# main.net
KiCad netlist of a schematic drawn in Altium Designer
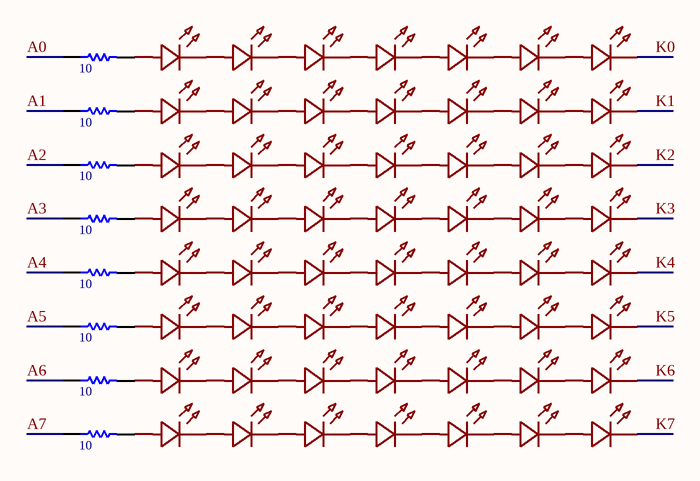
[diagram p0: main.SchDoc]

(export (version "E")
  (design (tool "Eeschema 10.0.6"))
  (components
    (comp (ref "R1")
      (value "10")
      (footprint "R2512")
      (description "10R 2512")
      (fields (field (name "LCSC PART NUMBER") "C173291"))
      (libsource (lib "Miscellaneous Devices") (part "RES"))
    )
    (comp (ref "R2")
      (value "10")
      (footprint "R2512")
      (description "10R 2512")
      (fields (field (name "LCSC PART NUMBER") "C173291"))
      (libsource (lib "Miscellaneous Devices") (part "RES"))
    )
    (comp (ref "R3")
      (value "10")
      (footprint "R2512")
      (description "10R 2512")
      (fields (field (name "LCSC PART NUMBER") "C173291"))
      (libsource (lib "Miscellaneous Devices") (part "RES"))
    )
    (comp (ref "R4")
      (value "10")
      (footprint "R2512")
      (description "10R 2512")
      (fields (field (name "LCSC PART NUMBER") "C173291"))
      (libsource (lib "Miscellaneous Devices") (part "RES"))
    )
    (comp (ref "R5")
      (value "10")
      (footprint "R2512")
      (description "10R 2512")
      (fields (field (name "LCSC PART NUMBER") "C173291"))
      (libsource (lib "Miscellaneous Devices") (part "RES"))
    )
    (comp (ref "R6")
      (value "10")
      (footprint "R2512")
      (description "10R 2512")
      (fields (field (name "LCSC PART NUMBER") "C173291"))
      (libsource (lib "Miscellaneous Devices") (part "RES"))
    )
    (comp (ref "R7")
      (value "10")
      (footprint "R2512")
      (description "10R 2512")
      (fields (field (name "LCSC PART NUMBER") "C173291"))
      (libsource (lib "Miscellaneous Devices") (part "RES"))
    )
    (comp (ref "R8")
      (value "10")
      (footprint "R2512")
      (description "10R 2512")
      (fields (field (name "LCSC PART NUMBER") "C173291"))
      (libsource (lib "Miscellaneous Devices") (part "RES"))
    )
    (comp (ref "U1")
      (value "~")
      (footprint "LED-SMD_7030")
      (libsource (lib "Schlib1") (part "XL-C3570P8S11-62C3C2"))
    )
    (comp (ref "U2")
      (value "~")
      (footprint "LED-SMD_7030")
      (libsource (lib "Schlib1") (part "XL-C3570P8S11-62C3C2"))
    )
    (comp (ref "U3")
      (value "~")
      (footprint "LED-SMD_7030")
      (libsource (lib "Schlib1") (part "XL-C3570P8S11-62C3C2"))
    )
    (comp (ref "U4")
      (value "~")
      (footprint "LED-SMD_7030")
      (libsource (lib "Schlib1") (part "XL-C3570P8S11-62C3C2"))
    )
    (comp (ref "U5")
      (value "~")
      (footprint "LED-SMD_7030")
      (libsource (lib "Schlib1") (part "XL-C3570P8S11-62C3C2"))
    )
    (comp (ref "U6")
      (value "~")
      (footprint "LED-SMD_7030")
      (libsource (lib "Schlib1") (part "XL-C3570P8S11-62C3C2"))
    )
    (comp (ref "U7")
      (value "~")
      (footprint "LED-SMD_7030")
      (libsource (lib "Schlib1") (part "XL-C3570P8S11-62C3C2"))
    )
    (comp (ref "U8")
      (value "~")
      (footprint "LED-SMD_7030")
      (libsource (lib "Schlib1") (part "XL-C3570P8S11-62C3C2"))
    )
    (comp (ref "U9")
      (value "~")
      (footprint "LED-SMD_7030")
      (libsource (lib "Schlib1") (part "XL-C3570P8S11-62C3C2"))
    )
    (comp (ref "U10")
      (value "~")
      (footprint "LED-SMD_7030")
      (libsource (lib "Schlib1") (part "XL-C3570P8S11-62C3C2"))
    )
    (comp (ref "U11")
      (value "~")
      (footprint "LED-SMD_7030")
      (libsource (lib "Schlib1") (part "XL-C3570P8S11-62C3C2"))
    )
    (comp (ref "U12")
      (value "~")
      (footprint "LED-SMD_7030")
      (libsource (lib "Schlib1") (part "XL-C3570P8S11-62C3C2"))
    )
    (comp (ref "U13")
      (value "~")
      (footprint "LED-SMD_7030")
      (libsource (lib "Schlib1") (part "XL-C3570P8S11-62C3C2"))
    )
    (comp (ref "U14")
      (value "~")
      (footprint "LED-SMD_7030")
      (libsource (lib "Schlib1") (part "XL-C3570P8S11-62C3C2"))
    )
    (comp (ref "U15")
      (value "~")
      (footprint "LED-SMD_7030")
      (libsource (lib "Schlib1") (part "XL-C3570P8S11-62C3C2"))
    )
    (comp (ref "U16")
      (value "~")
      (footprint "LED-SMD_7030")
      (libsource (lib "Schlib1") (part "XL-C3570P8S11-62C3C2"))
    )
    (comp (ref "U17")
      (value "~")
      (footprint "LED-SMD_7030")
      (libsource (lib "Schlib1") (part "XL-C3570P8S11-62C3C2"))
    )
    (comp (ref "U18")
      (value "~")
      (footprint "LED-SMD_7030")
      (libsource (lib "Schlib1") (part "XL-C3570P8S11-62C3C2"))
    )
    (comp (ref "U19")
      (value "~")
      (footprint "LED-SMD_7030")
      (libsource (lib "Schlib1") (part "XL-C3570P8S11-62C3C2"))
    )
    (comp (ref "U20")
      (value "~")
      (footprint "LED-SMD_7030")
      (libsource (lib "Schlib1") (part "XL-C3570P8S11-62C3C2"))
    )
    (comp (ref "U21")
      (value "~")
      (footprint "LED-SMD_7030")
      (libsource (lib "Schlib1") (part "XL-C3570P8S11-62C3C2"))
    )
    (comp (ref "U22")
      (value "~")
      (footprint "LED-SMD_7030")
      (libsource (lib "Schlib1") (part "XL-C3570P8S11-62C3C2"))
    )
    (comp (ref "U23")
      (value "~")
      (footprint "LED-SMD_7030")
      (libsource (lib "Schlib1") (part "XL-C3570P8S11-62C3C2"))
    )
    (comp (ref "U24")
      (value "~")
      (footprint "LED-SMD_7030")
      (libsource (lib "Schlib1") (part "XL-C3570P8S11-62C3C2"))
    )
    (comp (ref "U25")
      (value "~")
      (footprint "LED-SMD_7030")
      (libsource (lib "Schlib1") (part "XL-C3570P8S11-62C3C2"))
    )
    (comp (ref "U26")
      (value "~")
      (footprint "LED-SMD_7030")
      (libsource (lib "Schlib1") (part "XL-C3570P8S11-62C3C2"))
    )
    (comp (ref "U27")
      (value "~")
      (footprint "LED-SMD_7030")
      (libsource (lib "Schlib1") (part "XL-C3570P8S11-62C3C2"))
    )
    (comp (ref "U28")
      (value "~")
      (footprint "LED-SMD_7030")
      (libsource (lib "Schlib1") (part "XL-C3570P8S11-62C3C2"))
    )
    (comp (ref "U29")
      (value "~")
      (footprint "LED-SMD_7030")
      (libsource (lib "Schlib1") (part "XL-C3570P8S11-62C3C2"))
    )
    (comp (ref "U30")
      (value "~")
      (footprint "LED-SMD_7030")
      (libsource (lib "Schlib1") (part "XL-C3570P8S11-62C3C2"))
    )
    (comp (ref "U31")
      (value "~")
      (footprint "LED-SMD_7030")
      (libsource (lib "Schlib1") (part "XL-C3570P8S11-62C3C2"))
    )
    (comp (ref "U32")
      (value "~")
      (footprint "LED-SMD_7030")
      (libsource (lib "Schlib1") (part "XL-C3570P8S11-62C3C2"))
    )
    (comp (ref "U33")
      (value "~")
      (footprint "LED-SMD_7030")
      (libsource (lib "Schlib1") (part "XL-C3570P8S11-62C3C2"))
    )
    (comp (ref "U34")
      (value "~")
      (footprint "LED-SMD_7030")
      (libsource (lib "Schlib1") (part "XL-C3570P8S11-62C3C2"))
    )
    (comp (ref "U35")
      (value "~")
      (footprint "LED-SMD_7030")
      (libsource (lib "Schlib1") (part "XL-C3570P8S11-62C3C2"))
    )
    (comp (ref "U36")
      (value "~")
      (footprint "LED-SMD_7030")
      (libsource (lib "Schlib1") (part "XL-C3570P8S11-62C3C2"))
    )
    (comp (ref "U37")
      (value "~")
      (footprint "LED-SMD_7030")
      (libsource (lib "Schlib1") (part "XL-C3570P8S11-62C3C2"))
    )
    (comp (ref "U38")
      (value "~")
      (footprint "LED-SMD_7030")
      (libsource (lib "Schlib1") (part "XL-C3570P8S11-62C3C2"))
    )
    (comp (ref "U39")
      (value "~")
      (footprint "LED-SMD_7030")
      (libsource (lib "Schlib1") (part "XL-C3570P8S11-62C3C2"))
    )
    (comp (ref "U40")
      (value "~")
      (footprint "LED-SMD_7030")
      (libsource (lib "Schlib1") (part "XL-C3570P8S11-62C3C2"))
    )
    (comp (ref "U41")
      (value "~")
      (footprint "LED-SMD_7030")
      (libsource (lib "Schlib1") (part "XL-C3570P8S11-62C3C2"))
    )
    (comp (ref "U42")
      (value "~")
      (footprint "LED-SMD_7030")
      (libsource (lib "Schlib1") (part "XL-C3570P8S11-62C3C2"))
    )
    (comp (ref "U43")
      (value "~")
      (footprint "LED-SMD_7030")
      (libsource (lib "Schlib1") (part "XL-C3570P8S11-62C3C2"))
    )
    (comp (ref "U44")
      (value "~")
      (footprint "LED-SMD_7030")
      (libsource (lib "Schlib1") (part "XL-C3570P8S11-62C3C2"))
    )
    (comp (ref "U45")
      (value "~")
      (footprint "LED-SMD_7030")
      (libsource (lib "Schlib1") (part "XL-C3570P8S11-62C3C2"))
    )
    (comp (ref "U46")
      (value "~")
      (footprint "LED-SMD_7030")
      (libsource (lib "Schlib1") (part "XL-C3570P8S11-62C3C2"))
    )
    (comp (ref "U47")
      (value "~")
      (footprint "LED-SMD_7030")
      (libsource (lib "Schlib1") (part "XL-C3570P8S11-62C3C2"))
    )
    (comp (ref "U48")
      (value "~")
      (footprint "LED-SMD_7030")
      (libsource (lib "Schlib1") (part "XL-C3570P8S11-62C3C2"))
    )
    (comp (ref "U49")
      (value "~")
      (footprint "LED-SMD_7030")
      (libsource (lib "Schlib1") (part "XL-C3570P8S11-62C3C2"))
    )
    (comp (ref "U50")
      (value "~")
      (footprint "LED-SMD_7030")
      (libsource (lib "Schlib1") (part "XL-C3570P8S11-62C3C2"))
    )
    (comp (ref "U51")
      (value "~")
      (footprint "LED-SMD_7030")
      (libsource (lib "Schlib1") (part "XL-C3570P8S11-62C3C2"))
    )
    (comp (ref "U52")
      (value "~")
      (footprint "LED-SMD_7030")
      (libsource (lib "Schlib1") (part "XL-C3570P8S11-62C3C2"))
    )
    (comp (ref "U53")
      (value "~")
      (footprint "LED-SMD_7030")
      (libsource (lib "Schlib1") (part "XL-C3570P8S11-62C3C2"))
    )
    (comp (ref "U54")
      (value "~")
      (footprint "LED-SMD_7030")
      (libsource (lib "Schlib1") (part "XL-C3570P8S11-62C3C2"))
    )
    (comp (ref "U55")
      (value "~")
      (footprint "LED-SMD_7030")
      (libsource (lib "Schlib1") (part "XL-C3570P8S11-62C3C2"))
    )
    (comp (ref "U56")
      (value "~")
      (footprint "LED-SMD_7030")
      (libsource (lib "Schlib1") (part "XL-C3570P8S11-62C3C2"))
    )
  )
  (nets
    (net (code "1") (name "/A0") (class "Default")
      (node (ref "R1") (pin "1") (pinfunction "1_1") (pintype "passive"))
    )
    (net (code "2") (name "/A1") (class "Default")
      (node (ref "R2") (pin "1") (pinfunction "1_1") (pintype "passive"))
    )
    (net (code "3") (name "/A2") (class "Default")
      (node (ref "R3") (pin "1") (pinfunction "1_1") (pintype "passive"))
    )
    (net (code "4") (name "/A3") (class "Default")
      (node (ref "R4") (pin "1") (pinfunction "1_1") (pintype "passive"))
    )
    (net (code "5") (name "/A4") (class "Default")
      (node (ref "R5") (pin "1") (pinfunction "1_1") (pintype "passive"))
    )
    (net (code "6") (name "/A5") (class "Default")
      (node (ref "R6") (pin "1") (pinfunction "1_1") (pintype "passive"))
    )
    (net (code "7") (name "/A6") (class "Default")
      (node (ref "R7") (pin "1") (pinfunction "1_1") (pintype "passive"))
    )
    (net (code "8") (name "/A7") (class "Default")
      (node (ref "R8") (pin "1") (pinfunction "1_1") (pintype "passive"))
    )
    (net (code "9") (name "/K0") (class "Default")
      (node (ref "U7") (pin "2") (pinfunction "K_2") (pintype "passive"))
    )
    (net (code "10") (name "/K1") (class "Default")
      (node (ref "U14") (pin "2") (pinfunction "K_2") (pintype "passive"))
    )
    (net (code "11") (name "/K2") (class "Default")
      (node (ref "U21") (pin "2") (pinfunction "K_2") (pintype "passive"))
    )
    (net (code "12") (name "/K3") (class "Default")
      (node (ref "U28") (pin "2") (pinfunction "K_2") (pintype "passive"))
    )
    (net (code "13") (name "/K4") (class "Default")
      (node (ref "U35") (pin "2") (pinfunction "K_2") (pintype "passive"))
    )
    (net (code "14") (name "/K5") (class "Default")
      (node (ref "U42") (pin "2") (pinfunction "K_2") (pintype "passive"))
    )
    (net (code "15") (name "/K6") (class "Default")
      (node (ref "U49") (pin "2") (pinfunction "K_2") (pintype "passive"))
    )
    (net (code "16") (name "/K7") (class "Default")
      (node (ref "U56") (pin "2") (pinfunction "K_2") (pintype "passive"))
    )
    (net (code "17") (name "Net-(U1-A)") (class "Default")
      (node (ref "R1") (pin "2") (pinfunction "2_2") (pintype "passive"))
      (node (ref "U1") (pin "1") (pinfunction "A_1") (pintype "passive"))
    )
    (net (code "18") (name "Net-(U1-K)") (class "Default")
      (node (ref "U1") (pin "2") (pinfunction "K_2") (pintype "passive"))
      (node (ref "U2") (pin "1") (pinfunction "A_1") (pintype "passive"))
    )
    (net (code "19") (name "Net-(U2-K)") (class "Default")
      (node (ref "U2") (pin "2") (pinfunction "K_2") (pintype "passive"))
      (node (ref "U3") (pin "1") (pinfunction "A_1") (pintype "passive"))
    )
    (net (code "20") (name "Net-(U3-K)") (class "Default")
      (node (ref "U3") (pin "2") (pinfunction "K_2") (pintype "passive"))
      (node (ref "U4") (pin "1") (pinfunction "A_1") (pintype "passive"))
    )
    (net (code "21") (name "Net-(U4-K)") (class "Default")
      (node (ref "U4") (pin "2") (pinfunction "K_2") (pintype "passive"))
      (node (ref "U5") (pin "1") (pinfunction "A_1") (pintype "passive"))
    )
    (net (code "22") (name "Net-(U5-K)") (class "Default")
      (node (ref "U5") (pin "2") (pinfunction "K_2") (pintype "passive"))
      (node (ref "U6") (pin "1") (pinfunction "A_1") (pintype "passive"))
    )
    (net (code "23") (name "Net-(U6-K)") (class "Default")
      (node (ref "U6") (pin "2") (pinfunction "K_2") (pintype "passive"))
      (node (ref "U7") (pin "1") (pinfunction "A_1") (pintype "passive"))
    )
    (net (code "24") (name "Net-(U8-A)") (class "Default")
      (node (ref "R2") (pin "2") (pinfunction "2_2") (pintype "passive"))
      (node (ref "U8") (pin "1") (pinfunction "A_1") (pintype "passive"))
    )
    (net (code "25") (name "Net-(U8-K)") (class "Default")
      (node (ref "U8") (pin "2") (pinfunction "K_2") (pintype "passive"))
      (node (ref "U9") (pin "1") (pinfunction "A_1") (pintype "passive"))
    )
    (net (code "26") (name "Net-(U10-A)") (class "Default")
      (node (ref "U10") (pin "1") (pinfunction "A_1") (pintype "passive"))
      (node (ref "U9") (pin "2") (pinfunction "K_2") (pintype "passive"))
    )
    (net (code "27") (name "Net-(U10-K)") (class "Default")
      (node (ref "U10") (pin "2") (pinfunction "K_2") (pintype "passive"))
      (node (ref "U11") (pin "1") (pinfunction "A_1") (pintype "passive"))
    )
    (net (code "28") (name "Net-(U11-K)") (class "Default")
      (node (ref "U11") (pin "2") (pinfunction "K_2") (pintype "passive"))
      (node (ref "U12") (pin "1") (pinfunction "A_1") (pintype "passive"))
    )
    (net (code "29") (name "Net-(U12-K)") (class "Default")
      (node (ref "U12") (pin "2") (pinfunction "K_2") (pintype "passive"))
      (node (ref "U13") (pin "1") (pinfunction "A_1") (pintype "passive"))
    )
    (net (code "30") (name "Net-(U13-K)") (class "Default")
      (node (ref "U13") (pin "2") (pinfunction "K_2") (pintype "passive"))
      (node (ref "U14") (pin "1") (pinfunction "A_1") (pintype "passive"))
    )
    (net (code "31") (name "Net-(U15-A)") (class "Default")
      (node (ref "R3") (pin "2") (pinfunction "2_2") (pintype "passive"))
      (node (ref "U15") (pin "1") (pinfunction "A_1") (pintype "passive"))
    )
    (net (code "32") (name "Net-(U15-K)") (class "Default")
      (node (ref "U15") (pin "2") (pinfunction "K_2") (pintype "passive"))
      (node (ref "U16") (pin "1") (pinfunction "A_1") (pintype "passive"))
    )
    (net (code "33") (name "Net-(U16-K)") (class "Default")
      (node (ref "U16") (pin "2") (pinfunction "K_2") (pintype "passive"))
      (node (ref "U17") (pin "1") (pinfunction "A_1") (pintype "passive"))
    )
    (net (code "34") (name "Net-(U17-K)") (class "Default")
      (node (ref "U17") (pin "2") (pinfunction "K_2") (pintype "passive"))
      (node (ref "U18") (pin "1") (pinfunction "A_1") (pintype "passive"))
    )
    (net (code "35") (name "Net-(U18-K)") (class "Default")
      (node (ref "U18") (pin "2") (pinfunction "K_2") (pintype "passive"))
      (node (ref "U19") (pin "1") (pinfunction "A_1") (pintype "passive"))
    )
    (net (code "36") (name "Net-(U19-K)") (class "Default")
      (node (ref "U19") (pin "2") (pinfunction "K_2") (pintype "passive"))
      (node (ref "U20") (pin "1") (pinfunction "A_1") (pintype "passive"))
    )
    (net (code "37") (name "Net-(U20-K)") (class "Default")
      (node (ref "U20") (pin "2") (pinfunction "K_2") (pintype "passive"))
      (node (ref "U21") (pin "1") (pinfunction "A_1") (pintype "passive"))
    )
    (net (code "38") (name "Net-(U22-A)") (class "Default")
      (node (ref "R4") (pin "2") (pinfunction "2_2") (pintype "passive"))
      (node (ref "U22") (pin "1") (pinfunction "A_1") (pintype "passive"))
    )
    (net (code "39") (name "Net-(U22-K)") (class "Default")
      (node (ref "U22") (pin "2") (pinfunction "K_2") (pintype "passive"))
      (node (ref "U23") (pin "1") (pinfunction "A_1") (pintype "passive"))
    )
    (net (code "40") (name "Net-(U23-K)") (class "Default")
      (node (ref "U23") (pin "2") (pinfunction "K_2") (pintype "passive"))
      (node (ref "U24") (pin "1") (pinfunction "A_1") (pintype "passive"))
    )
    (net (code "41") (name "Net-(U24-K)") (class "Default")
      (node (ref "U24") (pin "2") (pinfunction "K_2") (pintype "passive"))
      (node (ref "U25") (pin "1") (pinfunction "A_1") (pintype "passive"))
    )
    (net (code "42") (name "Net-(U25-K)") (class "Default")
      (node (ref "U25") (pin "2") (pinfunction "K_2") (pintype "passive"))
      (node (ref "U26") (pin "1") (pinfunction "A_1") (pintype "passive"))
    )
    (net (code "43") (name "Net-(U26-K)") (class "Default")
      (node (ref "U26") (pin "2") (pinfunction "K_2") (pintype "passive"))
      (node (ref "U27") (pin "1") (pinfunction "A_1") (pintype "passive"))
    )
    (net (code "44") (name "Net-(U27-K)") (class "Default")
      (node (ref "U27") (pin "2") (pinfunction "K_2") (pintype "passive"))
      (node (ref "U28") (pin "1") (pinfunction "A_1") (pintype "passive"))
    )
    (net (code "45") (name "Net-(U29-A)") (class "Default")
      (node (ref "R5") (pin "2") (pinfunction "2_2") (pintype "passive"))
      (node (ref "U29") (pin "1") (pinfunction "A_1") (pintype "passive"))
    )
    (net (code "46") (name "Net-(U29-K)") (class "Default")
      (node (ref "U29") (pin "2") (pinfunction "K_2") (pintype "passive"))
      (node (ref "U30") (pin "1") (pinfunction "A_1") (pintype "passive"))
    )
    (net (code "47") (name "Net-(U30-K)") (class "Default")
      (node (ref "U30") (pin "2") (pinfunction "K_2") (pintype "passive"))
      (node (ref "U31") (pin "1") (pinfunction "A_1") (pintype "passive"))
    )
    (net (code "48") (name "Net-(U31-K)") (class "Default")
      (node (ref "U31") (pin "2") (pinfunction "K_2") (pintype "passive"))
      (node (ref "U32") (pin "1") (pinfunction "A_1") (pintype "passive"))
    )
    (net (code "49") (name "Net-(U32-K)") (class "Default")
      (node (ref "U32") (pin "2") (pinfunction "K_2") (pintype "passive"))
      (node (ref "U33") (pin "1") (pinfunction "A_1") (pintype "passive"))
    )
    (net (code "50") (name "Net-(U33-K)") (class "Default")
      (node (ref "U33") (pin "2") (pinfunction "K_2") (pintype "passive"))
      (node (ref "U34") (pin "1") (pinfunction "A_1") (pintype "passive"))
    )
    (net (code "51") (name "Net-(U34-K)") (class "Default")
      (node (ref "U34") (pin "2") (pinfunction "K_2") (pintype "passive"))
      (node (ref "U35") (pin "1") (pinfunction "A_1") (pintype "passive"))
    )
    (net (code "52") (name "Net-(U36-A)") (class "Default")
      (node (ref "R6") (pin "2") (pinfunction "2_2") (pintype "passive"))
      (node (ref "U36") (pin "1") (pinfunction "A_1") (pintype "passive"))
    )
    (net (code "53") (name "Net-(U36-K)") (class "Default")
      (node (ref "U36") (pin "2") (pinfunction "K_2") (pintype "passive"))
      (node (ref "U37") (pin "1") (pinfunction "A_1") (pintype "passive"))
    )
    (net (code "54") (name "Net-(U37-K)") (class "Default")
      (node (ref "U37") (pin "2") (pinfunction "K_2") (pintype "passive"))
      (node (ref "U38") (pin "1") (pinfunction "A_1") (pintype "passive"))
    )
    (net (code "55") (name "Net-(U38-K)") (class "Default")
      (node (ref "U38") (pin "2") (pinfunction "K_2") (pintype "passive"))
      (node (ref "U39") (pin "1") (pinfunction "A_1") (pintype "passive"))
    )
    (net (code "56") (name "Net-(U39-K)") (class "Default")
      (node (ref "U39") (pin "2") (pinfunction "K_2") (pintype "passive"))
      (node (ref "U40") (pin "1") (pinfunction "A_1") (pintype "passive"))
    )
    (net (code "57") (name "Net-(U40-K)") (class "Default")
      (node (ref "U40") (pin "2") (pinfunction "K_2") (pintype "passive"))
      (node (ref "U41") (pin "1") (pinfunction "A_1") (pintype "passive"))
    )
    (net (code "58") (name "Net-(U41-K)") (class "Default")
      (node (ref "U41") (pin "2") (pinfunction "K_2") (pintype "passive"))
      (node (ref "U42") (pin "1") (pinfunction "A_1") (pintype "passive"))
    )
    (net (code "59") (name "Net-(U43-A)") (class "Default")
      (node (ref "R7") (pin "2") (pinfunction "2_2") (pintype "passive"))
      (node (ref "U43") (pin "1") (pinfunction "A_1") (pintype "passive"))
    )
    (net (code "60") (name "Net-(U43-K)") (class "Default")
      (node (ref "U43") (pin "2") (pinfunction "K_2") (pintype "passive"))
      (node (ref "U44") (pin "1") (pinfunction "A_1") (pintype "passive"))
    )
    (net (code "61") (name "Net-(U44-K)") (class "Default")
      (node (ref "U44") (pin "2") (pinfunction "K_2") (pintype "passive"))
      (node (ref "U45") (pin "1") (pinfunction "A_1") (pintype "passive"))
    )
    (net (code "62") (name "Net-(U45-K)") (class "Default")
      (node (ref "U45") (pin "2") (pinfunction "K_2") (pintype "passive"))
      (node (ref "U46") (pin "1") (pinfunction "A_1") (pintype "passive"))
    )
    (net (code "63") (name "Net-(U46-K)") (class "Default")
      (node (ref "U46") (pin "2") (pinfunction "K_2") (pintype "passive"))
      (node (ref "U47") (pin "1") (pinfunction "A_1") (pintype "passive"))
    )
    (net (code "64") (name "Net-(U47-K)") (class "Default")
      (node (ref "U47") (pin "2") (pinfunction "K_2") (pintype "passive"))
      (node (ref "U48") (pin "1") (pinfunction "A_1") (pintype "passive"))
    )
    (net (code "65") (name "Net-(U48-K)") (class "Default")
      (node (ref "U48") (pin "2") (pinfunction "K_2") (pintype "passive"))
      (node (ref "U49") (pin "1") (pinfunction "A_1") (pintype "passive"))
    )
    (net (code "66") (name "Net-(U50-A)") (class "Default")
      (node (ref "R8") (pin "2") (pinfunction "2_2") (pintype "passive"))
      (node (ref "U50") (pin "1") (pinfunction "A_1") (pintype "passive"))
    )
    (net (code "67") (name "Net-(U50-K)") (class "Default")
      (node (ref "U50") (pin "2") (pinfunction "K_2") (pintype "passive"))
      (node (ref "U51") (pin "1") (pinfunction "A_1") (pintype "passive"))
    )
    (net (code "68") (name "Net-(U51-K)") (class "Default")
      (node (ref "U51") (pin "2") (pinfunction "K_2") (pintype "passive"))
      (node (ref "U52") (pin "1") (pinfunction "A_1") (pintype "passive"))
    )
    (net (code "69") (name "Net-(U52-K)") (class "Default")
      (node (ref "U52") (pin "2") (pinfunction "K_2") (pintype "passive"))
      (node (ref "U53") (pin "1") (pinfunction "A_1") (pintype "passive"))
    )
    (net (code "70") (name "Net-(U53-K)") (class "Default")
      (node (ref "U53") (pin "2") (pinfunction "K_2") (pintype "passive"))
      (node (ref "U54") (pin "1") (pinfunction "A_1") (pintype "passive"))
    )
    (net (code "71") (name "Net-(U54-K)") (class "Default")
      (node (ref "U54") (pin "2") (pinfunction "K_2") (pintype "passive"))
      (node (ref "U55") (pin "1") (pinfunction "A_1") (pintype "passive"))
    )
    (net (code "72") (name "Net-(U55-K)") (class "Default")
      (node (ref "U55") (pin "2") (pinfunction "K_2") (pintype "passive"))
      (node (ref "U56") (pin "1") (pinfunction "A_1") (pintype "passive"))
    )
  )
)
